# prize_delivery.net
KiCad netlist of a schematic drawn in EAGLE
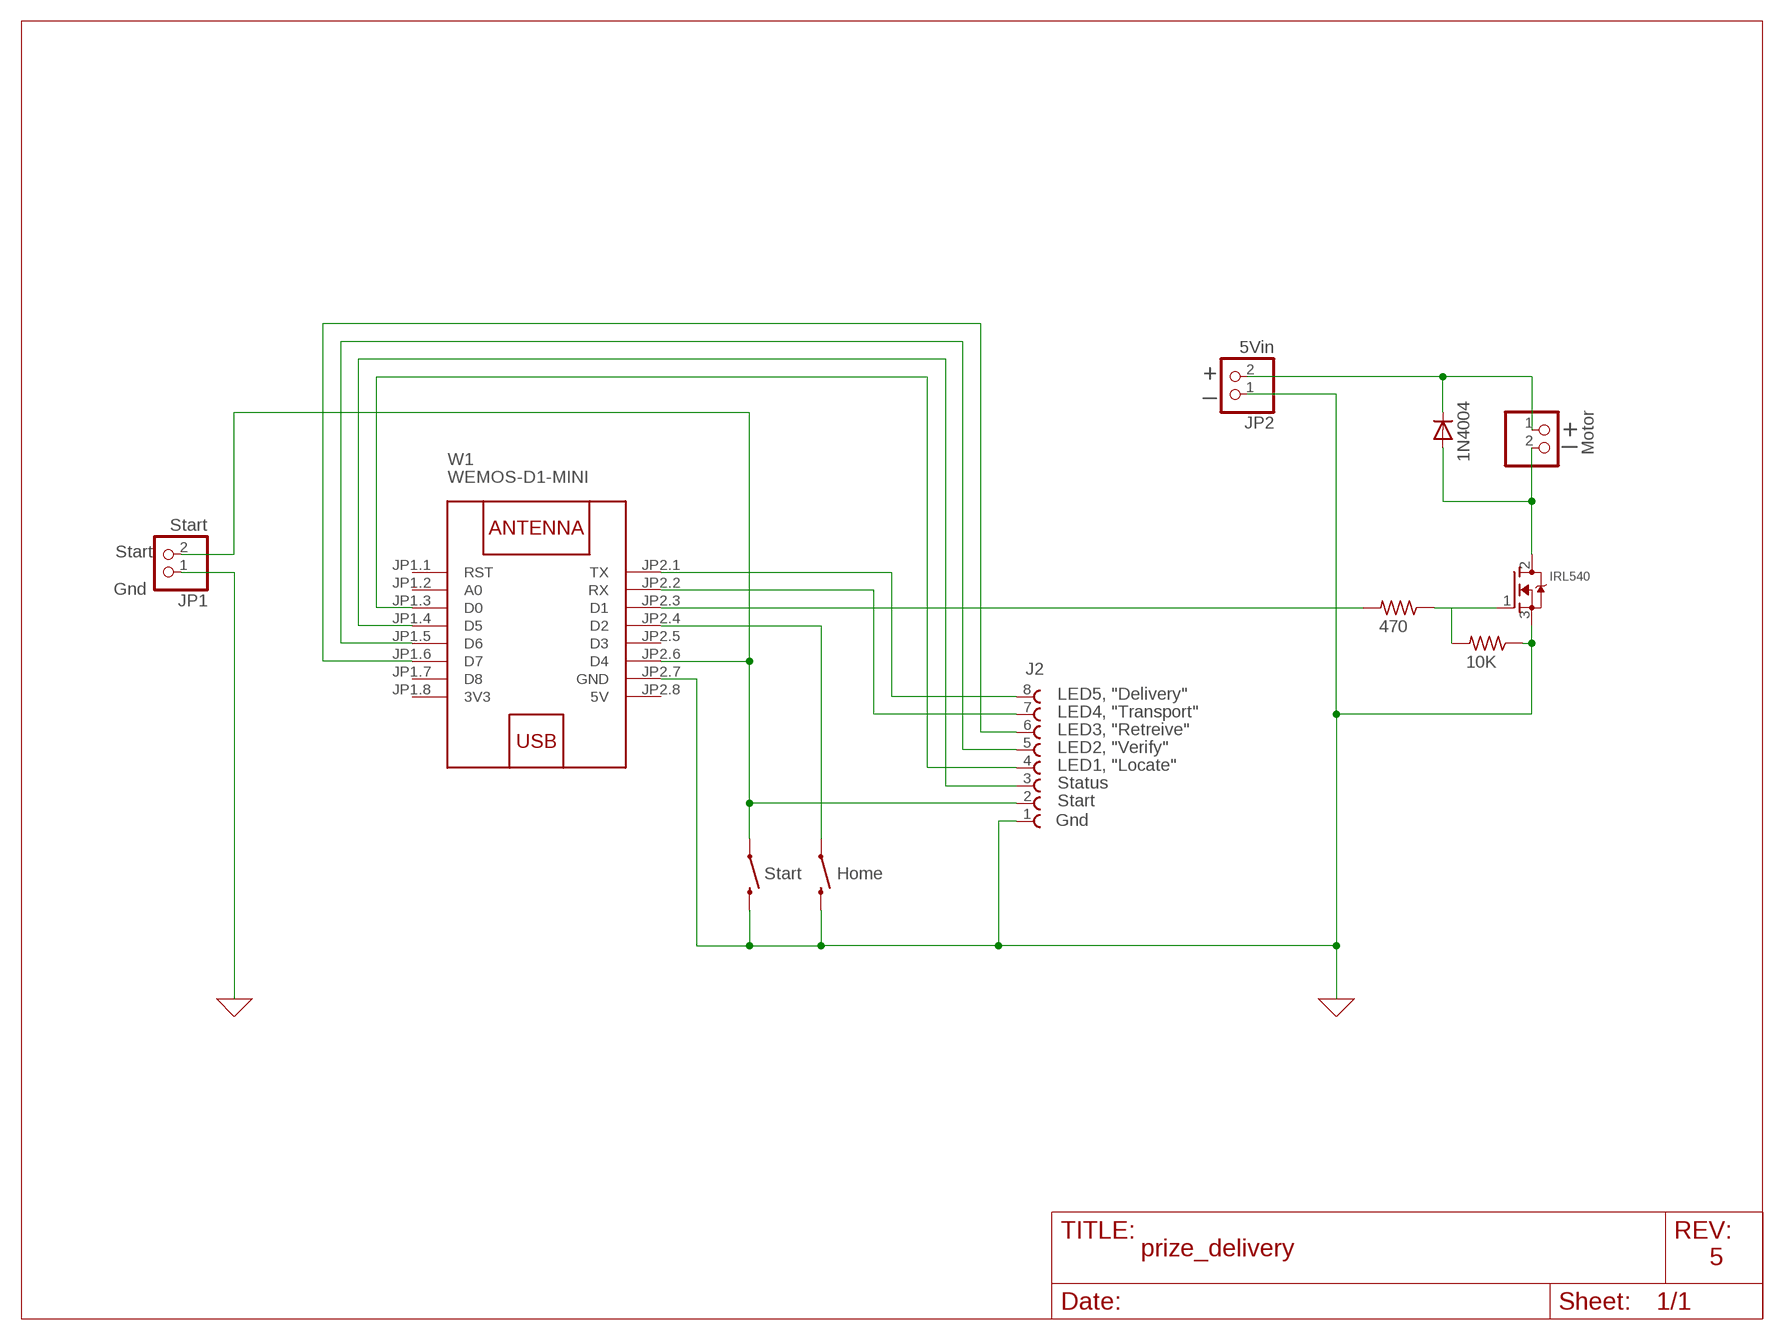
[diagram p0: schematic, sheet 1]

(export (version "E")
  (design (tool "Eeschema 10.0.6"))
  (components
    (comp (ref "360°")
      (value "MOMENTARY-SWITCH-SPST-PTH-6.0MM")
      (footprint "eagle-import:TACTILE_SWITCH_PTH_6.0MM")
      (libsource (lib "eagle-import") (part "MOMENTARY-SWITCH-SPST-PTH-6.0MM"))
    )
    (comp (ref "D1")
      (value "1N4004")
      (footprint "eagle-import:DO41-10")
      (libsource (lib "eagle-import") (part "1N4004"))
    )
    (comp (ref "J2")
      (value "691136710008")
      (footprint "eagle-import:691136710008")
      (libsource (lib "eagle-import") (part "691136710008"))
    )
    (comp (ref "JP1")
      (value "Start")
      (footprint "eagle-import:1X02")
      (libsource (lib "eagle-import") (part "PINHD-1X2"))
    )
    (comp (ref "JP2")
      (value "5Vin")
      (footprint "eagle-import:1X02")
      (libsource (lib "eagle-import") (part "PINHD-1X2"))
    )
    (comp (ref "JP3")
      (value "Motor")
      (footprint "eagle-import:1X02")
      (libsource (lib "eagle-import") (part "PINHD-1X2"))
    )
    (comp (ref "Q1")
      (value "IRL540")
      (footprint "eagle-import:TO220V")
      (libsource (lib "eagle-import") (part "MOSFET-NGDS_TO220V"))
    )
    (comp (ref "R2")
      (value "470")
      (footprint "eagle-import:0207_10")
      (libsource (lib "eagle-import") (part "R-US_0207/10"))
    )
    (comp (ref "R4")
      (value "10K")
      (footprint "eagle-import:0207_10")
      (libsource (lib "eagle-import") (part "R-US_0207/10"))
    )
    (comp (ref "START")
      (value "MOMENTARY-SWITCH-SPST-PTH-6.0MM")
      (footprint "eagle-import:TACTILE_SWITCH_PTH_6.0MM")
      (libsource (lib "eagle-import") (part "MOMENTARY-SWITCH-SPST-PTH-6.0MM"))
    )
    (comp (ref "W1")
      (value "WEMOS-D1-MINI")
      (footprint "eagle-import:WEMOS-D1-MINI")
      (libsource (lib "eagle-import") (part "WEMOS-D1-MINI"))
    )
  )
  (nets
    (net (code "1") (name "/3V3") (class "Default")
      (node (ref "W1") (pin "JP1.8") (pinfunction "3V3_JP1.8") (pintype "power_in"))
    )
    (net (code "2") (name "/5V") (class "Default")
      (node (ref "W1") (pin "JP2.8") (pinfunction "5V_JP2.8") (pintype "power_in"))
    )
    (net (code "3") (name "GND") (class "Default")
      (node (ref "360°") (pin "3") (pinfunction "2_3") (pintype "passive"))
      (node (ref "J2") (pin "1") (pinfunction "1_1") (pintype "passive"))
      (node (ref "JP1") (pin "1") (pinfunction "1_1") (pintype "passive"))
      (node (ref "JP2") (pin "1") (pinfunction "1_1") (pintype "passive"))
      (node (ref "Q1") (pin "3") (pinfunction "S_3") (pintype "bidirectional"))
      (node (ref "R4") (pin "1") (pinfunction "1_1") (pintype "passive"))
      (node (ref "START") (pin "3") (pinfunction "2_3") (pintype "passive"))
      (node (ref "W1") (pin "JP2.7") (pinfunction "GND_JP2.7") (pintype "power_in"))
    )
    (net (code "4") (name "Net-(D1-PadC)") (class "Default")
      (node (ref "D1") (pin "C") (pinfunction "C_C") (pintype "passive"))
      (node (ref "JP2") (pin "2") (pinfunction "2_2") (pintype "passive"))
      (node (ref "JP3") (pin "1") (pinfunction "1_1") (pintype "passive"))
    )
    (net (code "5") (name "Net-(Q1-D)") (class "Default")
      (node (ref "D1") (pin "A") (pinfunction "A_A") (pintype "passive"))
      (node (ref "JP3") (pin "2") (pinfunction "2_2") (pintype "passive"))
      (node (ref "Q1") (pin "2") (pinfunction "D_2") (pintype "bidirectional"))
    )
    (net (code "6") (name "Net-(Q1-G)") (class "Default")
      (node (ref "Q1") (pin "1") (pinfunction "G_1") (pintype "bidirectional"))
      (node (ref "R2") (pin "1") (pinfunction "1_1") (pintype "passive"))
      (node (ref "R4") (pin "2") (pinfunction "2_2") (pintype "passive"))
    )
    (net (code "7") (name "Net-(W1-D0)") (class "Default")
      (node (ref "J2") (pin "4") (pinfunction "4_4") (pintype "passive"))
      (node (ref "W1") (pin "JP1.3") (pinfunction "D0_JP1.3") (pintype "bidirectional"))
    )
    (net (code "8") (name "Net-(W1-D1)") (class "Default")
      (node (ref "R2") (pin "2") (pinfunction "2_2") (pintype "passive"))
      (node (ref "W1") (pin "JP2.3") (pinfunction "D1_JP2.3") (pintype "bidirectional"))
    )
    (net (code "9") (name "Net-(W1-D2)") (class "Default")
      (node (ref "360°") (pin "1") (pinfunction "1_1") (pintype "passive"))
      (node (ref "W1") (pin "JP2.4") (pinfunction "D2_JP2.4") (pintype "bidirectional"))
    )
    (net (code "10") (name "Net-(W1-D4)") (class "Default")
      (node (ref "J2") (pin "2") (pinfunction "2_2") (pintype "passive"))
      (node (ref "JP1") (pin "2") (pinfunction "2_2") (pintype "passive"))
      (node (ref "START") (pin "1") (pinfunction "1_1") (pintype "passive"))
      (node (ref "W1") (pin "JP2.6") (pinfunction "D4_JP2.6") (pintype "bidirectional"))
    )
    (net (code "11") (name "Net-(W1-D5)") (class "Default")
      (node (ref "J2") (pin "3") (pinfunction "3_3") (pintype "passive"))
      (node (ref "W1") (pin "JP1.4") (pinfunction "D5_JP1.4") (pintype "bidirectional"))
    )
    (net (code "12") (name "Net-(W1-D6)") (class "Default")
      (node (ref "J2") (pin "5") (pinfunction "5_5") (pintype "passive"))
      (node (ref "W1") (pin "JP1.5") (pinfunction "D6_JP1.5") (pintype "bidirectional"))
    )
    (net (code "13") (name "Net-(W1-D7)") (class "Default")
      (node (ref "J2") (pin "6") (pinfunction "6_6") (pintype "passive"))
      (node (ref "W1") (pin "JP1.6") (pinfunction "D7_JP1.6") (pintype "bidirectional"))
    )
    (net (code "14") (name "Net-(W1-RX)") (class "Default")
      (node (ref "J2") (pin "7") (pinfunction "7_7") (pintype "passive"))
      (node (ref "W1") (pin "JP2.2") (pinfunction "RX_JP2.2") (pintype "bidirectional"))
    )
    (net (code "15") (name "Net-(W1-TX)") (class "Default")
      (node (ref "J2") (pin "8") (pinfunction "8_8") (pintype "passive"))
      (node (ref "W1") (pin "JP2.1") (pinfunction "TX_JP2.1") (pintype "bidirectional"))
    )
    (net (code "16") (name "unconnected-(W1-A0-PadJP1.2)") (class "Default")
      (node (ref "W1") (pin "JP1.2") (pinfunction "A0_JP1.2") (pintype "bidirectional"))
    )
    (net (code "17") (name "unconnected-(W1-D3-PadJP2.5)") (class "Default")
      (node (ref "W1") (pin "JP2.5") (pinfunction "D3_JP2.5") (pintype "bidirectional"))
    )
    (net (code "18") (name "unconnected-(W1-D8-PadJP1.7)") (class "Default")
      (node (ref "W1") (pin "JP1.7") (pinfunction "D8_JP1.7") (pintype "bidirectional"))
    )
    (net (code "19") (name "unconnected-(W1-RST-PadJP1.1)") (class "Default")
      (node (ref "W1") (pin "JP1.1") (pinfunction "RST_JP1.1") (pintype "bidirectional"))
    )
  )
)
